# satellite.net
KiCad netlist of a schematic drawn in EAGLE
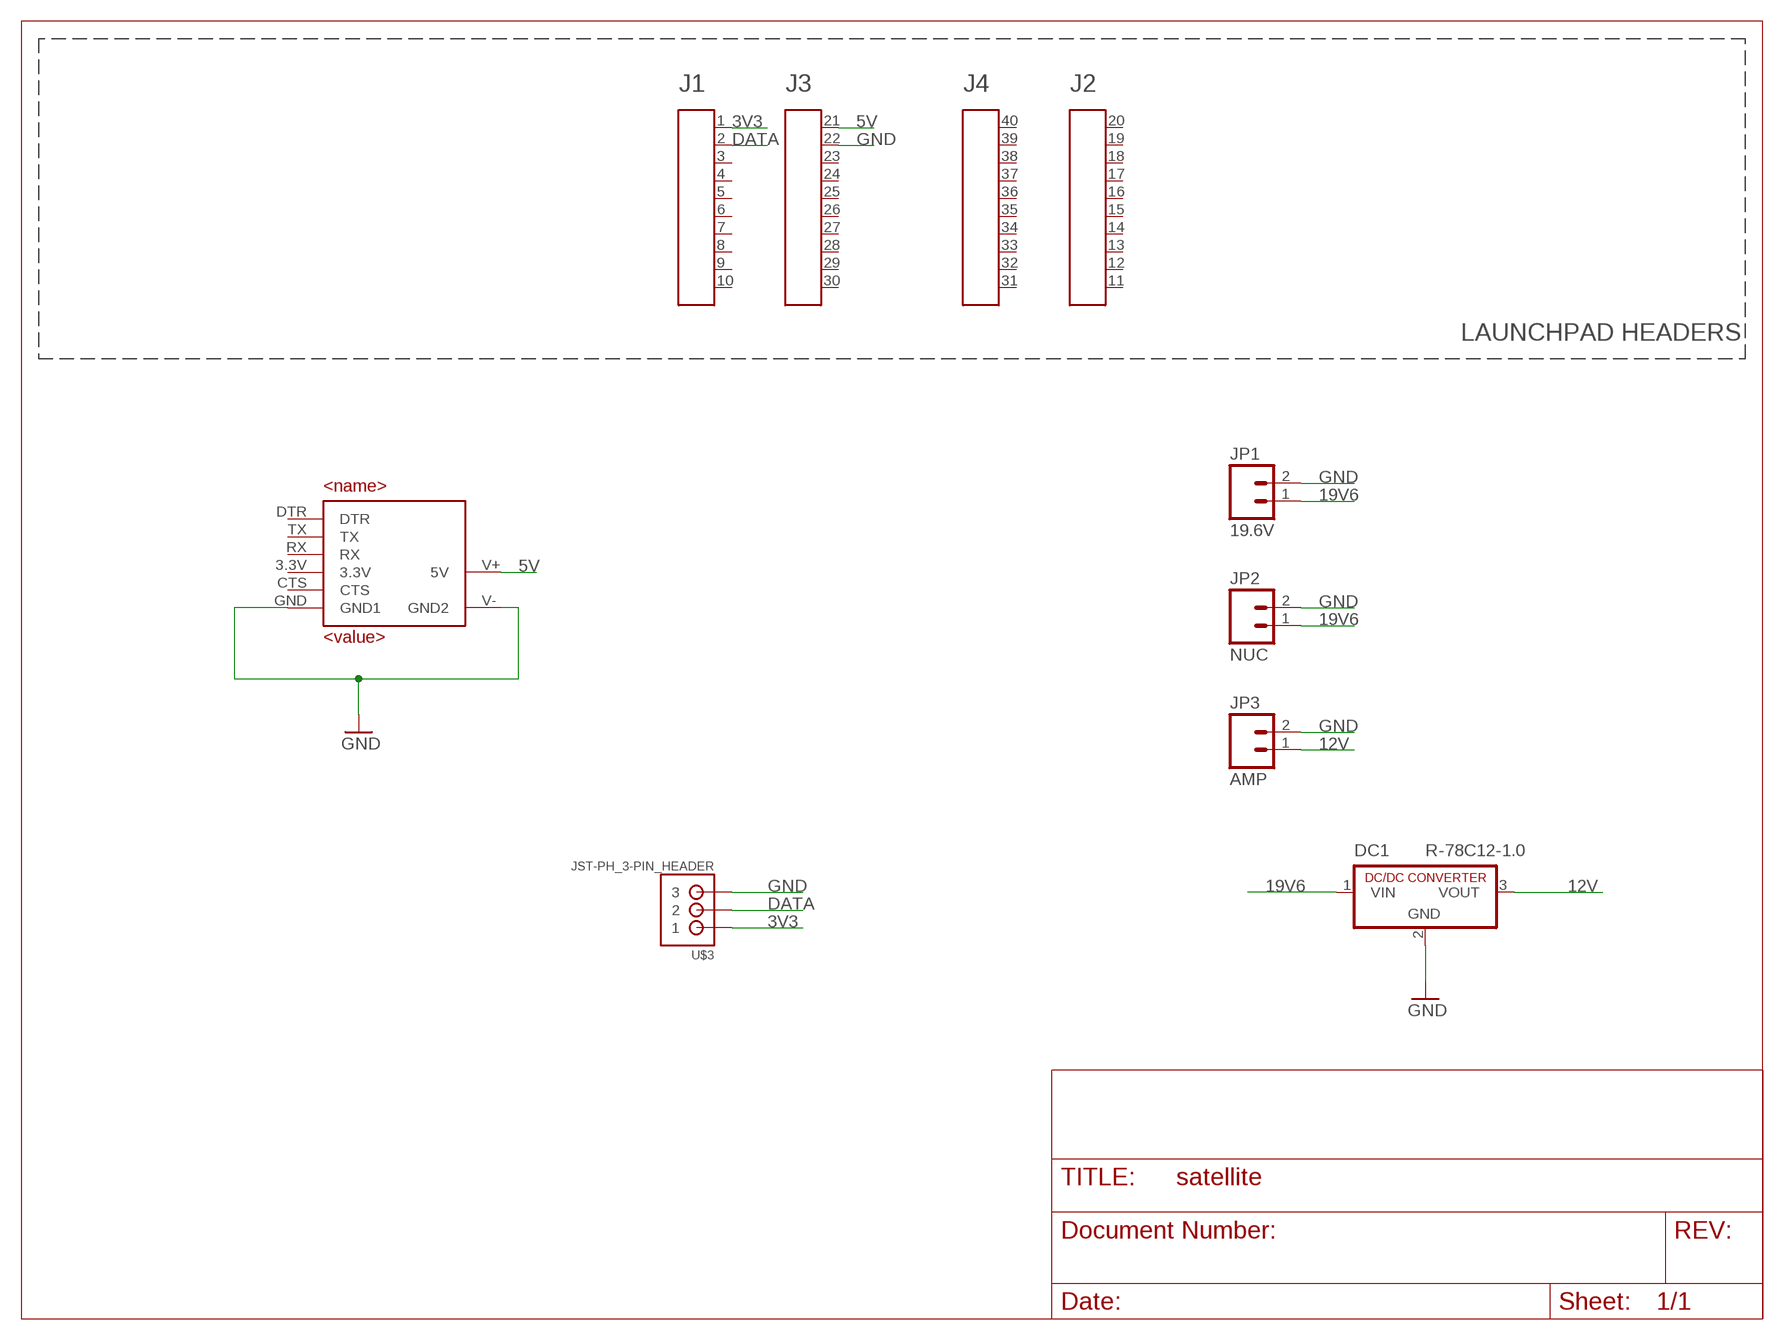
[diagram p0: schematic, sheet 1]

(export (version "E")
  (design (tool "Eeschema 10.0.6"))
  (components
    (comp (ref "A1")
      (value "HEADER4X10-BOOSTERPACK")
      (footprint "eagle-import:4X10-BOOSTERPACK")
      (libsource (lib "eagle-import") (part "HEADER4X10-BOOSTERPACK"))
    )
    (comp (ref "DC1")
      (value "R-78C12-1.0")
      (footprint "eagle-import:SIP3")
      (libsource (lib "eagle-import") (part "R-78C-1.012"))
    )
    (comp (ref "JP1")
      (value "19.6V")
      (footprint "eagle-import:SCREWTERMINAL-3.5MM-2")
      (libsource (lib "eagle-import") (part "M023.5MM"))
    )
    (comp (ref "JP2")
      (value "NUC")
      (footprint "eagle-import:SCREWTERMINAL-3.5MM-2")
      (libsource (lib "eagle-import") (part "M023.5MM"))
    )
    (comp (ref "JP3")
      (value "AMP")
      (footprint "eagle-import:SCREWTERMINAL-3.5MM-2")
      (libsource (lib "eagle-import") (part "M023.5MM"))
    )
    (comp (ref "U$3")
      (value "JST-PH_3-PIN_HEADER")
      (footprint "eagle-import:JST_B3B-PH_HEADER")
      (libsource (lib "eagle-import") (part "JST-PH_3-PIN_HEADER"))
    )
    (comp (ref "U1")
      (value "9DOF")
      (footprint "eagle-import:9DOF")
      (libsource (lib "eagle-import") (part "9DOF"))
    )
  )
  (nets
    (net (code "1") (name "/3V3") (class "Default")
      (node (ref "A1") (pin "1") (pinfunction "P$1_1") (pintype "bidirectional"))
      (node (ref "U$3") (pin "P1") (pinfunction "1_P1") (pintype "bidirectional"))
    )
    (net (code "2") (name "/5V") (class "Default")
      (node (ref "A1") (pin "21") (pinfunction "P$21_21") (pintype "bidirectional"))
      (node (ref "U1") (pin "V+") (pinfunction "5V_V+") (pintype "bidirectional"))
    )
    (net (code "3") (name "/12V") (class "Default")
      (node (ref "DC1") (pin "3") (pinfunction "VOUT_3") (pintype "passive"))
      (node (ref "JP3") (pin "1") (pinfunction "1_1") (pintype "passive"))
    )
    (net (code "4") (name "/19V6") (class "Default")
      (node (ref "DC1") (pin "1") (pinfunction "VIN_1") (pintype "passive"))
      (node (ref "JP1") (pin "1") (pinfunction "1_1") (pintype "passive"))
      (node (ref "JP2") (pin "1") (pinfunction "1_1") (pintype "passive"))
    )
    (net (code "5") (name "/DATA") (class "Default")
      (node (ref "A1") (pin "2") (pinfunction "P$2_2") (pintype "bidirectional"))
      (node (ref "U$3") (pin "P2") (pinfunction "2_P2") (pintype "bidirectional"))
    )
    (net (code "6") (name "GND") (class "Default")
      (node (ref "A1") (pin "22") (pinfunction "P$22_22") (pintype "bidirectional"))
      (node (ref "DC1") (pin "2") (pinfunction "GND_2") (pintype "passive"))
      (node (ref "JP1") (pin "2") (pinfunction "2_2") (pintype "passive"))
      (node (ref "JP2") (pin "2") (pinfunction "2_2") (pintype "passive"))
      (node (ref "JP3") (pin "2") (pinfunction "2_2") (pintype "passive"))
      (node (ref "U$3") (pin "P3") (pinfunction "3_P3") (pintype "bidirectional"))
      (node (ref "U1") (pin "GND") (pinfunction "GND1_GND") (pintype "bidirectional"))
      (node (ref "U1") (pin "V-") (pinfunction "GND2_V-") (pintype "bidirectional"))
    )
    (net (code "7") (name "unconnected-(A1-P$3-Pad3)") (class "Default")
      (node (ref "A1") (pin "3") (pinfunction "P$3_3") (pintype "bidirectional"))
    )
    (net (code "8") (name "unconnected-(A1-P$4-Pad4)") (class "Default")
      (node (ref "A1") (pin "4") (pinfunction "P$4_4") (pintype "bidirectional"))
    )
    (net (code "9") (name "unconnected-(A1-P$5-Pad5)") (class "Default")
      (node (ref "A1") (pin "5") (pinfunction "P$5_5") (pintype "bidirectional"))
    )
    (net (code "10") (name "unconnected-(A1-P$6-Pad6)") (class "Default")
      (node (ref "A1") (pin "6") (pinfunction "P$6_6") (pintype "bidirectional"))
    )
    (net (code "11") (name "unconnected-(A1-P$7-Pad7)") (class "Default")
      (node (ref "A1") (pin "7") (pinfunction "P$7_7") (pintype "bidirectional"))
    )
    (net (code "12") (name "unconnected-(A1-P$8-Pad8)") (class "Default")
      (node (ref "A1") (pin "8") (pinfunction "P$8_8") (pintype "bidirectional"))
    )
    (net (code "13") (name "unconnected-(A1-P$9-Pad9)") (class "Default")
      (node (ref "A1") (pin "9") (pinfunction "P$9_9") (pintype "bidirectional"))
    )
    (net (code "14") (name "unconnected-(A1-P$10-Pad10)") (class "Default")
      (node (ref "A1") (pin "10") (pinfunction "P$10_10") (pintype "bidirectional"))
    )
    (net (code "15") (name "unconnected-(A1-P$11-Pad11)") (class "Default")
      (node (ref "A1") (pin "11") (pinfunction "P$11_11") (pintype "bidirectional"))
    )
    (net (code "16") (name "unconnected-(A1-P$12-Pad12)") (class "Default")
      (node (ref "A1") (pin "12") (pinfunction "P$12_12") (pintype "bidirectional"))
    )
    (net (code "17") (name "unconnected-(A1-P$13-Pad13)") (class "Default")
      (node (ref "A1") (pin "13") (pinfunction "P$13_13") (pintype "bidirectional"))
    )
    (net (code "18") (name "unconnected-(A1-P$14-Pad14)") (class "Default")
      (node (ref "A1") (pin "14") (pinfunction "P$14_14") (pintype "bidirectional"))
    )
    (net (code "19") (name "unconnected-(A1-P$15-Pad15)") (class "Default")
      (node (ref "A1") (pin "15") (pinfunction "P$15_15") (pintype "bidirectional"))
    )
    (net (code "20") (name "unconnected-(A1-P$16-Pad16)") (class "Default")
      (node (ref "A1") (pin "16") (pinfunction "P$16_16") (pintype "bidirectional"))
    )
    (net (code "21") (name "unconnected-(A1-P$17-Pad17)") (class "Default")
      (node (ref "A1") (pin "17") (pinfunction "P$17_17") (pintype "bidirectional"))
    )
    (net (code "22") (name "unconnected-(A1-P$18-Pad18)") (class "Default")
      (node (ref "A1") (pin "18") (pinfunction "P$18_18") (pintype "bidirectional"))
    )
    (net (code "23") (name "unconnected-(A1-P$19-Pad19)") (class "Default")
      (node (ref "A1") (pin "19") (pinfunction "P$19_19") (pintype "bidirectional"))
    )
    (net (code "24") (name "unconnected-(A1-P$20-Pad20)") (class "Default")
      (node (ref "A1") (pin "20") (pinfunction "P$20_20") (pintype "bidirectional"))
    )
    (net (code "25") (name "unconnected-(A1-P$23-Pad23)") (class "Default")
      (node (ref "A1") (pin "23") (pinfunction "P$23_23") (pintype "bidirectional"))
    )
    (net (code "26") (name "unconnected-(A1-P$24-Pad24)") (class "Default")
      (node (ref "A1") (pin "24") (pinfunction "P$24_24") (pintype "bidirectional"))
    )
    (net (code "27") (name "unconnected-(A1-P$25-Pad25)") (class "Default")
      (node (ref "A1") (pin "25") (pinfunction "P$25_25") (pintype "bidirectional"))
    )
    (net (code "28") (name "unconnected-(A1-P$26-Pad26)") (class "Default")
      (node (ref "A1") (pin "26") (pinfunction "P$26_26") (pintype "bidirectional"))
    )
    (net (code "29") (name "unconnected-(A1-P$27-Pad27)") (class "Default")
      (node (ref "A1") (pin "27") (pinfunction "P$27_27") (pintype "bidirectional"))
    )
    (net (code "30") (name "unconnected-(A1-P$28-Pad28)") (class "Default")
      (node (ref "A1") (pin "28") (pinfunction "P$28_28") (pintype "bidirectional"))
    )
    (net (code "31") (name "unconnected-(A1-P$29-Pad29)") (class "Default")
      (node (ref "A1") (pin "29") (pinfunction "P$29_29") (pintype "bidirectional"))
    )
    (net (code "32") (name "unconnected-(A1-P$30-Pad30)") (class "Default")
      (node (ref "A1") (pin "30") (pinfunction "P$30_30") (pintype "bidirectional"))
    )
    (net (code "33") (name "unconnected-(A1-P$31-Pad31)") (class "Default")
      (node (ref "A1") (pin "31") (pinfunction "P$31_31") (pintype "bidirectional"))
    )
    (net (code "34") (name "unconnected-(A1-P$32-Pad32)") (class "Default")
      (node (ref "A1") (pin "32") (pinfunction "P$32_32") (pintype "bidirectional"))
    )
    (net (code "35") (name "unconnected-(A1-P$33-Pad33)") (class "Default")
      (node (ref "A1") (pin "33") (pinfunction "P$33_33") (pintype "bidirectional"))
    )
    (net (code "36") (name "unconnected-(A1-P$34-Pad34)") (class "Default")
      (node (ref "A1") (pin "34") (pinfunction "P$34_34") (pintype "bidirectional"))
    )
    (net (code "37") (name "unconnected-(A1-P$35-Pad35)") (class "Default")
      (node (ref "A1") (pin "35") (pinfunction "P$35_35") (pintype "bidirectional"))
    )
    (net (code "38") (name "unconnected-(A1-P$36-Pad36)") (class "Default")
      (node (ref "A1") (pin "36") (pinfunction "P$36_36") (pintype "bidirectional"))
    )
    (net (code "39") (name "unconnected-(A1-P$37-Pad37)") (class "Default")
      (node (ref "A1") (pin "37") (pinfunction "P$37_37") (pintype "bidirectional"))
    )
    (net (code "40") (name "unconnected-(A1-P$38-Pad38)") (class "Default")
      (node (ref "A1") (pin "38") (pinfunction "P$38_38") (pintype "bidirectional"))
    )
    (net (code "41") (name "unconnected-(A1-P$39-Pad39)") (class "Default")
      (node (ref "A1") (pin "39") (pinfunction "P$39_39") (pintype "bidirectional"))
    )
    (net (code "42") (name "unconnected-(A1-P$40-Pad40)") (class "Default")
      (node (ref "A1") (pin "40") (pinfunction "P$40_40") (pintype "bidirectional"))
    )
    (net (code "43") (name "unconnected-(U1-Pad3.3V)") (class "Default")
      (node (ref "U1") (pin "3.3V") (pinfunction "3.3V_3.3V") (pintype "bidirectional"))
    )
    (net (code "44") (name "unconnected-(U1-PadCTS)") (class "Default")
      (node (ref "U1") (pin "CTS") (pinfunction "CTS_CTS") (pintype "bidirectional"))
    )
    (net (code "45") (name "unconnected-(U1-PadDTR)") (class "Default")
      (node (ref "U1") (pin "DTR") (pinfunction "DTR_DTR") (pintype "bidirectional"))
    )
    (net (code "46") (name "unconnected-(U1-PadRX)") (class "Default")
      (node (ref "U1") (pin "RX") (pinfunction "RX_RX") (pintype "bidirectional"))
    )
    (net (code "47") (name "unconnected-(U1-PadTX)") (class "Default")
      (node (ref "U1") (pin "TX") (pinfunction "TX_TX") (pintype "bidirectional"))
    )
  )
)
